# DRG_SPI169-240x280_V1_0_001.net
KiCad netlist of a schematic drawn in EasyEDA Pro
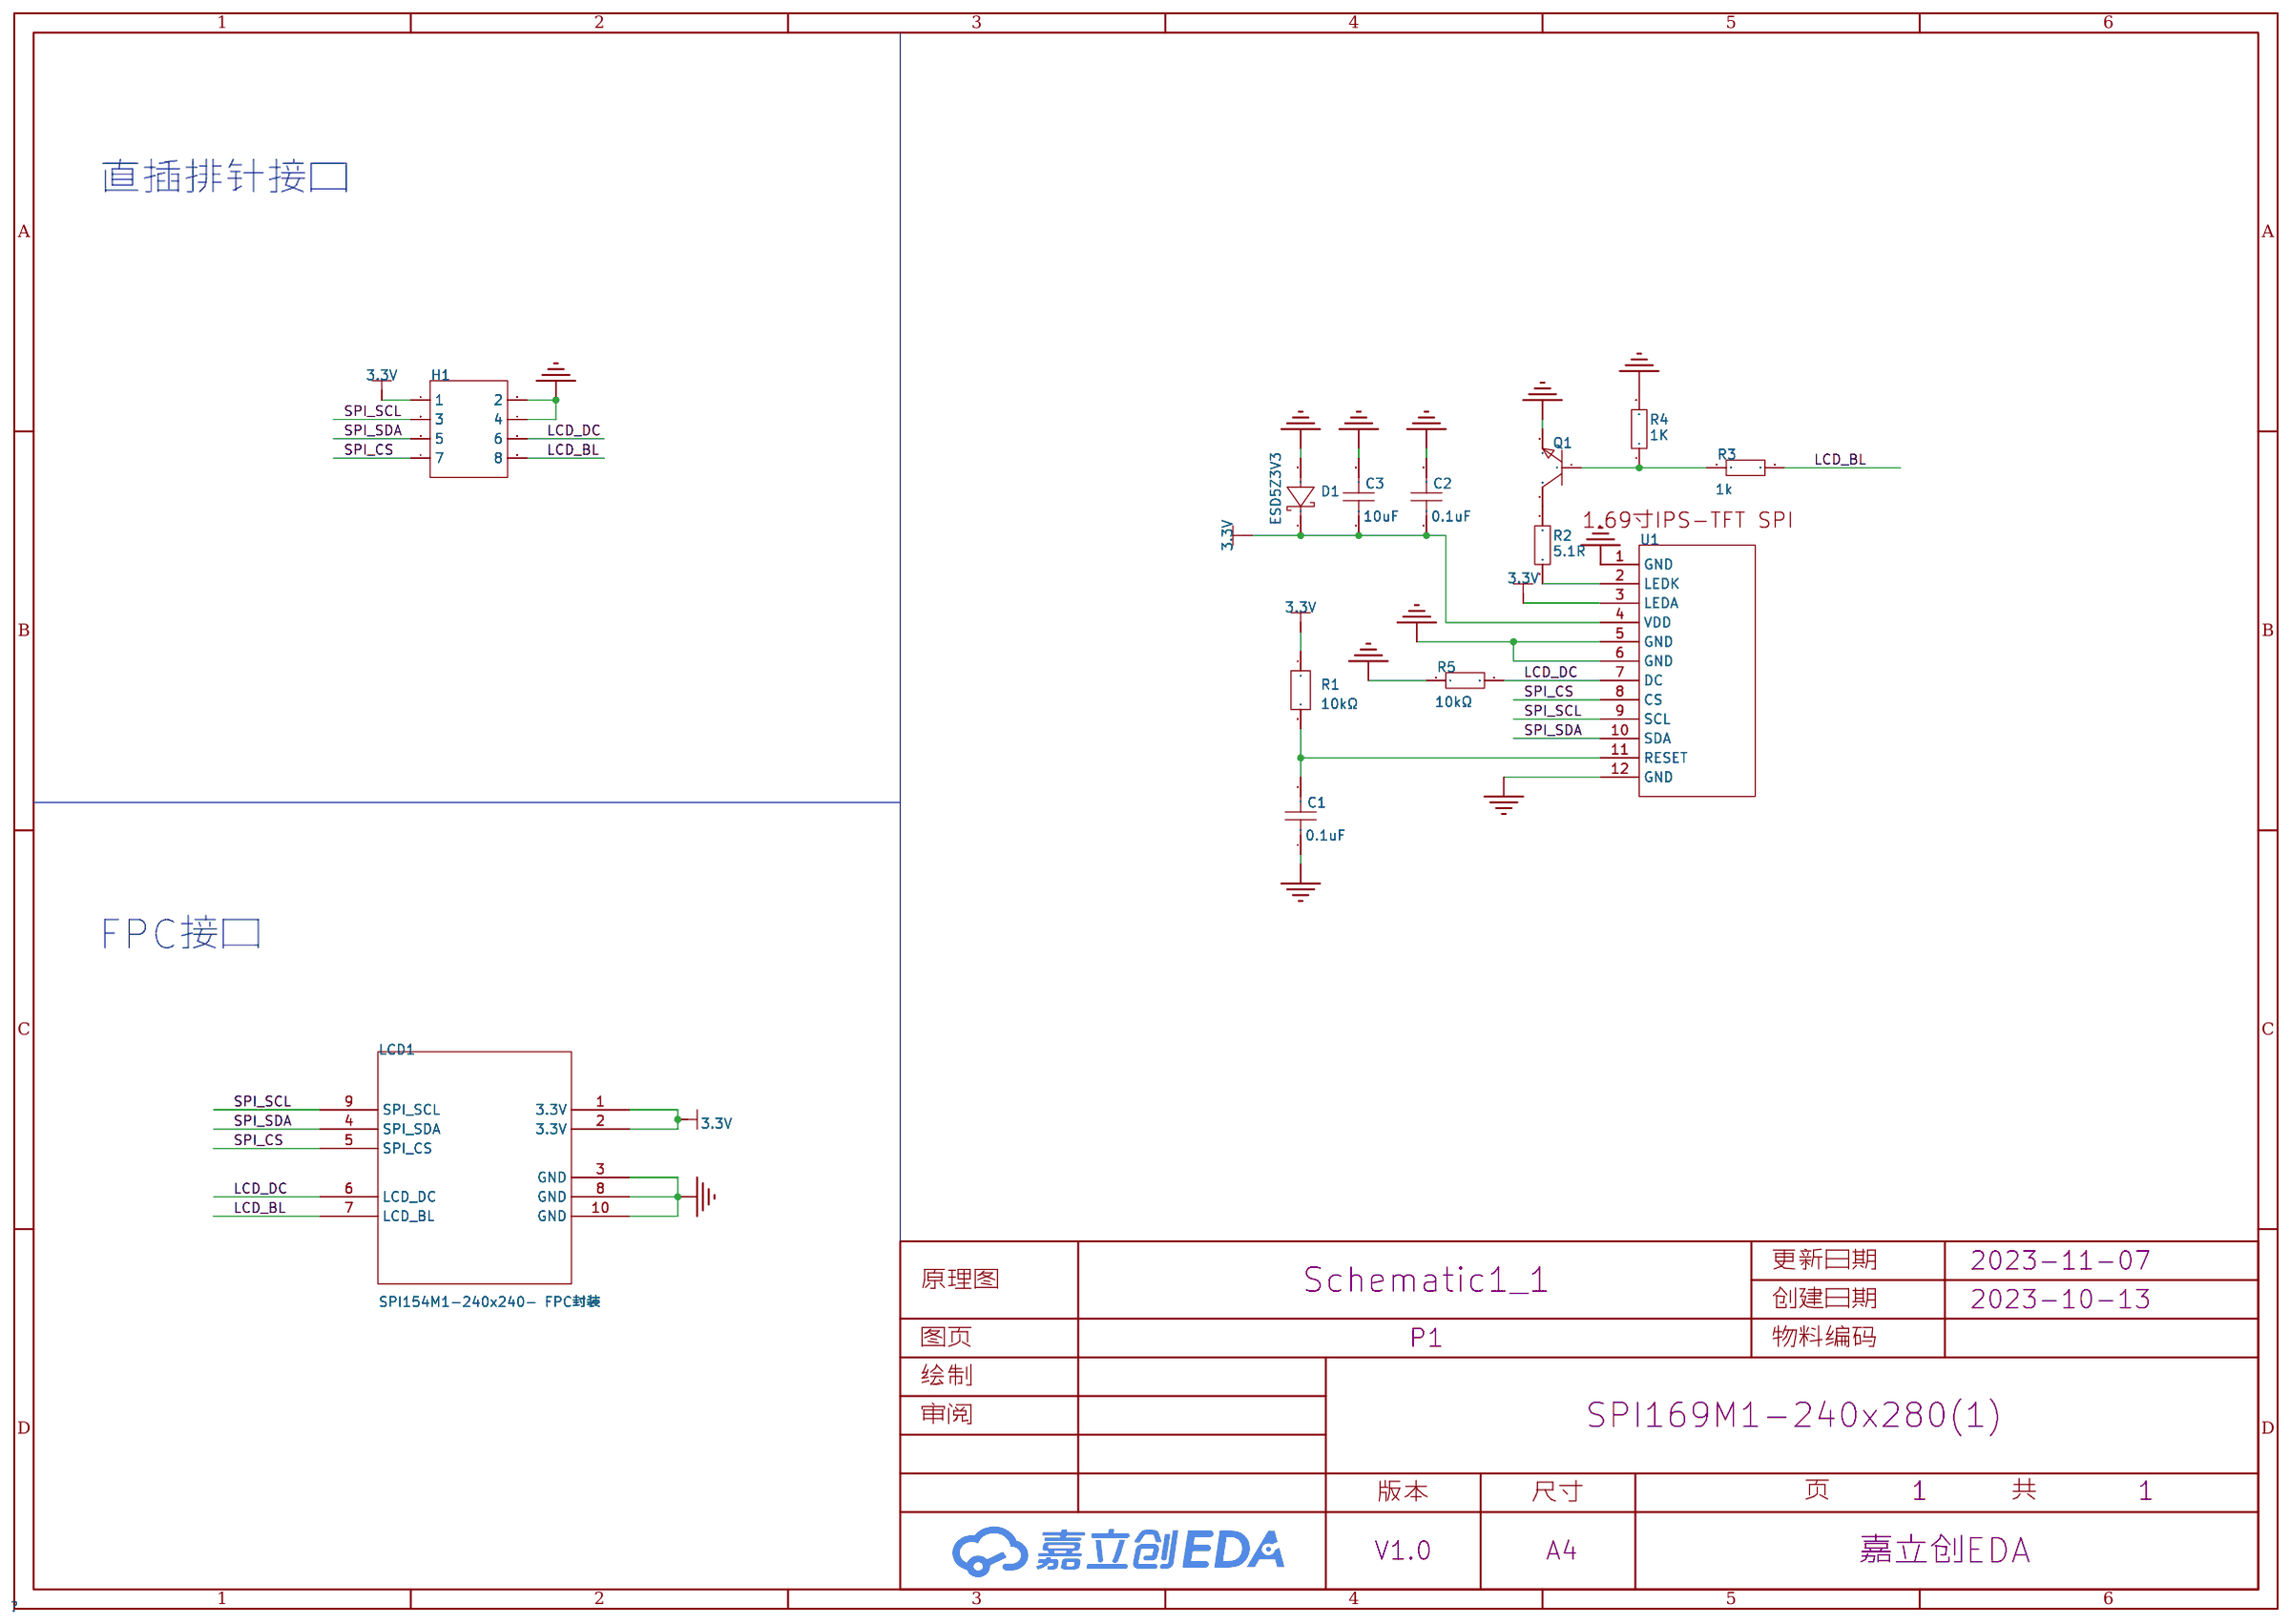
[diagram p0: schematic sheet]

(export (version "E")
  (design (tool "Eeschema 10.0.6"))
  (components
    (comp (ref "C1")
      (value "0.1uF")
      (footprint "easyedapro:C0603")
      (description "容值:10uF;精度:±20%;额定电压:16V;材质(温度系数):-;")
      (fields (field (name "Manufacturer Part") "10uF") (field (name "Manufacturer") "SAMSUNG(三星)"))
      (libsource (lib "easyedapro") (part "10UF"))
    )
    (comp (ref "C2")
      (value "0.1uF")
      (footprint "easyedapro:C0603")
      (description "容值:10uF;精度:±20%;额定电压:16V;材质(温度系数):-;")
      (fields (field (name "Manufacturer Part") "10uF") (field (name "Manufacturer") "SAMSUNG(三星)"))
      (libsource (lib "easyedapro") (part "10UF"))
    )
    (comp (ref "C3")
      (value "10uF")
      (footprint "easyedapro:C0603")
      (description "容值:10uF;精度:±20%;额定电压:16V;材质(温度系数):-;")
      (fields (field (name "Manufacturer") "SAMSUNG(三星)"))
      (libsource (lib "easyedapro") (part "10UF"))
    )
    (comp (ref "D1")
      (value "ESD5Z3V3")
      (footprint "easyedapro:SOD-523_L1.2-W0.8-LS1.6-RD")
      (fields (field (name "Manufacturer") "TWGMC(台湾迪嘉)"))
      (libsource (lib "easyedapro") (part "ESD5Z3V3_C727160"))
    )
    (comp (ref "H1")
      (value "~")
      (footprint "easyedapro:HDR-TH_8P-P2.54-V-F-R2-C4-S2.54-1")
      (libsource (lib "easyedapro") (part "HDR-F-2.54_2x4"))
    )
    (comp (ref "LCD1")
      (value "SPI154M1-240x240- FPC封装")
      (libsource (lib "easyedapro") (part "SPI154M1-240x240- FPC封装"))
    )
    (comp (ref "Q1")
      (value "~")
      (footprint "easyedapro:S8050_SOT-23")
      (libsource (lib "easyedapro") (part "NPN"))
    )
    (comp (ref "R1")
      (value "10kΩ")
      (footprint "easyedapro:R0603")
      (description "电阻类型:薄膜电阻;阻值:10kΩ;精度:±0.1%;功率:100mW;")
      (fields (field (name "Manufacturer Part") "AT0603BRD0710KL") (field (name "Manufacturer") "YAGEO(国巨)"))
      (libsource (lib "easyedapro") (part "AT0603BRD0710KL"))
    )
    (comp (ref "R2")
      (value "5.1R")
      (footprint "easyedapro:R0603")
      (description "电阻类型:厚膜电阻;阻值:10kΩ;精度:±1%;功率:100mW;")
      (fields (field (name "Manufacturer Part") "ETCR0603F10K0K9") (field (name "Manufacturer") "RESI(开步睿思）"))
      (libsource (lib "easyedapro") (part "ETCR0603F10K0K9"))
    )
    (comp (ref "R3")
      (value "1k")
      (footprint "easyedapro:R0603")
      (description "电阻类型:厚膜电阻;阻值:10kΩ;精度:±1%;功率:100mW;")
      (fields (field (name "Manufacturer Part") "ETCR0603F10K0K9") (field (name "Manufacturer") "RESI(开步睿思）"))
      (libsource (lib "easyedapro") (part "ETCR0603F10K0K9"))
    )
    (comp (ref "R4")
      (value "1K")
      (footprint "easyedapro:R0603")
      (description "电阻类型:厚膜电阻;阻值:10kΩ;精度:±1%;功率:100mW;")
      (fields (field (name "Manufacturer Part") "ETCR0603F10K0K9") (field (name "Manufacturer") "RESI(开步睿思）"))
      (libsource (lib "easyedapro") (part "ETCR0603F10K0K9"))
    )
    (comp (ref "R5")
      (value "10kΩ")
      (footprint "easyedapro:R0603")
      (description "电阻类型:厚膜电阻;阻值:10kΩ;精度:±1%;功率:100mW;")
      (fields (field (name "Manufacturer Part") "ETCR0603F10K0K9") (field (name "Manufacturer") "RESI(开步睿思）"))
      (libsource (lib "easyedapro") (part "ETCR0603F10K0K9"))
    )
    (comp (ref "U1") (value "~") (libsource (lib "easyedapro") (part "symbol_7dee")))
  )
  (nets
    (net (code "1") (name "/LCD_BL") (class "Default")
      (node (ref "H1") (pin "8") (pinfunction "8_8") (pintype "input"))
      (node (ref "LCD1") (pin "7") (pinfunction "LCD_BL_7") (pintype "input"))
      (node (ref "R3") (pin "2") (pinfunction "2_2") (pintype "input"))
    )
    (net (code "2") (name "/LCD_DC") (class "Default")
      (node (ref "H1") (pin "6") (pinfunction "6_6") (pintype "input"))
      (node (ref "LCD1") (pin "6") (pinfunction "LCD_DC_6") (pintype "input"))
      (node (ref "R5") (pin "2") (pinfunction "2_2") (pintype "input"))
      (node (ref "U1") (pin "7") (pinfunction "DC_7") (pintype "input"))
    )
    (net (code "3") (name "/SPI_CS") (class "Default")
      (node (ref "H1") (pin "7") (pinfunction "7_7") (pintype "input"))
      (node (ref "LCD1") (pin "5") (pinfunction "SPI_CS_5") (pintype "input"))
      (node (ref "U1") (pin "8") (pinfunction "CS_8") (pintype "input"))
    )
    (net (code "4") (name "/SPI_SCL") (class "Default")
      (node (ref "H1") (pin "3") (pinfunction "3_3") (pintype "input"))
      (node (ref "LCD1") (pin "9") (pinfunction "SPI_SCL_9") (pintype "input"))
      (node (ref "U1") (pin "9") (pinfunction "SCL_9") (pintype "input"))
    )
    (net (code "5") (name "/SPI_SDA") (class "Default")
      (node (ref "H1") (pin "5") (pinfunction "5_5") (pintype "input"))
      (node (ref "LCD1") (pin "4") (pinfunction "SPI_SDA_4") (pintype "input"))
      (node (ref "U1") (pin "10") (pinfunction "SDA_10") (pintype "input"))
    )
    (net (code "6") (name "3.3V") (class "Default")
      (node (ref "C2") (pin "1") (pinfunction "1_1") (pintype "input"))
      (node (ref "C3") (pin "1") (pinfunction "1_1") (pintype "input"))
      (node (ref "D1") (pin "1") (pinfunction "1_1") (pintype "input"))
      (node (ref "H1") (pin "1") (pinfunction "1_1") (pintype "input"))
      (node (ref "LCD1") (pin "1") (pinfunction "3.3V_1") (pintype "input"))
      (node (ref "LCD1") (pin "2") (pinfunction "3.3V_2") (pintype "input"))
      (node (ref "R1") (pin "1") (pinfunction "1_1") (pintype "input"))
      (node (ref "U1") (pin "3") (pinfunction "LEDA_3") (pintype "input"))
      (node (ref "U1") (pin "4") (pinfunction "VDD_4") (pintype "input"))
    )
    (net (code "7") (name "GND") (class "Default")
      (node (ref "C1") (pin "1") (pinfunction "1_1") (pintype "input"))
      (node (ref "C2") (pin "2") (pinfunction "2_2") (pintype "input"))
      (node (ref "C3") (pin "2") (pinfunction "2_2") (pintype "input"))
      (node (ref "D1") (pin "2") (pinfunction "2_2") (pintype "input"))
      (node (ref "H1") (pin "2") (pinfunction "2_2") (pintype "input"))
      (node (ref "H1") (pin "4") (pinfunction "4_4") (pintype "input"))
      (node (ref "LCD1") (pin "10") (pinfunction "GND_10") (pintype "input"))
      (node (ref "LCD1") (pin "3") (pinfunction "GND_3") (pintype "input"))
      (node (ref "LCD1") (pin "8") (pinfunction "GND_8") (pintype "input"))
      (node (ref "Q1") (pin "2") (pinfunction "2_2") (pintype "unspecified"))
      (node (ref "R4") (pin "2") (pinfunction "2_2") (pintype "input"))
      (node (ref "R5") (pin "1") (pinfunction "1_1") (pintype "input"))
      (node (ref "U1") (pin "1") (pinfunction "GND_1") (pintype "input"))
      (node (ref "U1") (pin "12") (pinfunction "GND_12") (pintype "input"))
      (node (ref "U1") (pin "5") (pinfunction "GND_5") (pintype "input"))
      (node (ref "U1") (pin "6") (pinfunction "GND_6") (pintype "input"))
    )
    (net (code "8") (name "Net-(Q1-Pad1)") (class "Default")
      (node (ref "Q1") (pin "1") (pinfunction "1_1") (pintype "unspecified"))
      (node (ref "R3") (pin "1") (pinfunction "1_1") (pintype "input"))
      (node (ref "R4") (pin "1") (pinfunction "1_1") (pintype "input"))
    )
    (net (code "9") (name "Net-(Q1-Pad3)") (class "Default")
      (node (ref "Q1") (pin "3") (pinfunction "3_3") (pintype "unspecified"))
      (node (ref "R2") (pin "2") (pinfunction "2_2") (pintype "input"))
    )
    (net (code "10") (name "Net-(U1-LEDK)") (class "Default")
      (node (ref "R2") (pin "1") (pinfunction "1_1") (pintype "input"))
      (node (ref "U1") (pin "2") (pinfunction "LEDK_2") (pintype "input"))
    )
    (net (code "11") (name "Net-(U1-RESET)") (class "Default")
      (node (ref "C1") (pin "2") (pinfunction "2_2") (pintype "input"))
      (node (ref "R1") (pin "2") (pinfunction "2_2") (pintype "input"))
      (node (ref "U1") (pin "11") (pinfunction "RESET_11") (pintype "input"))
    )
  )
)
